# design.net
KiCad netlist of a schematic drawn in EasyEDA
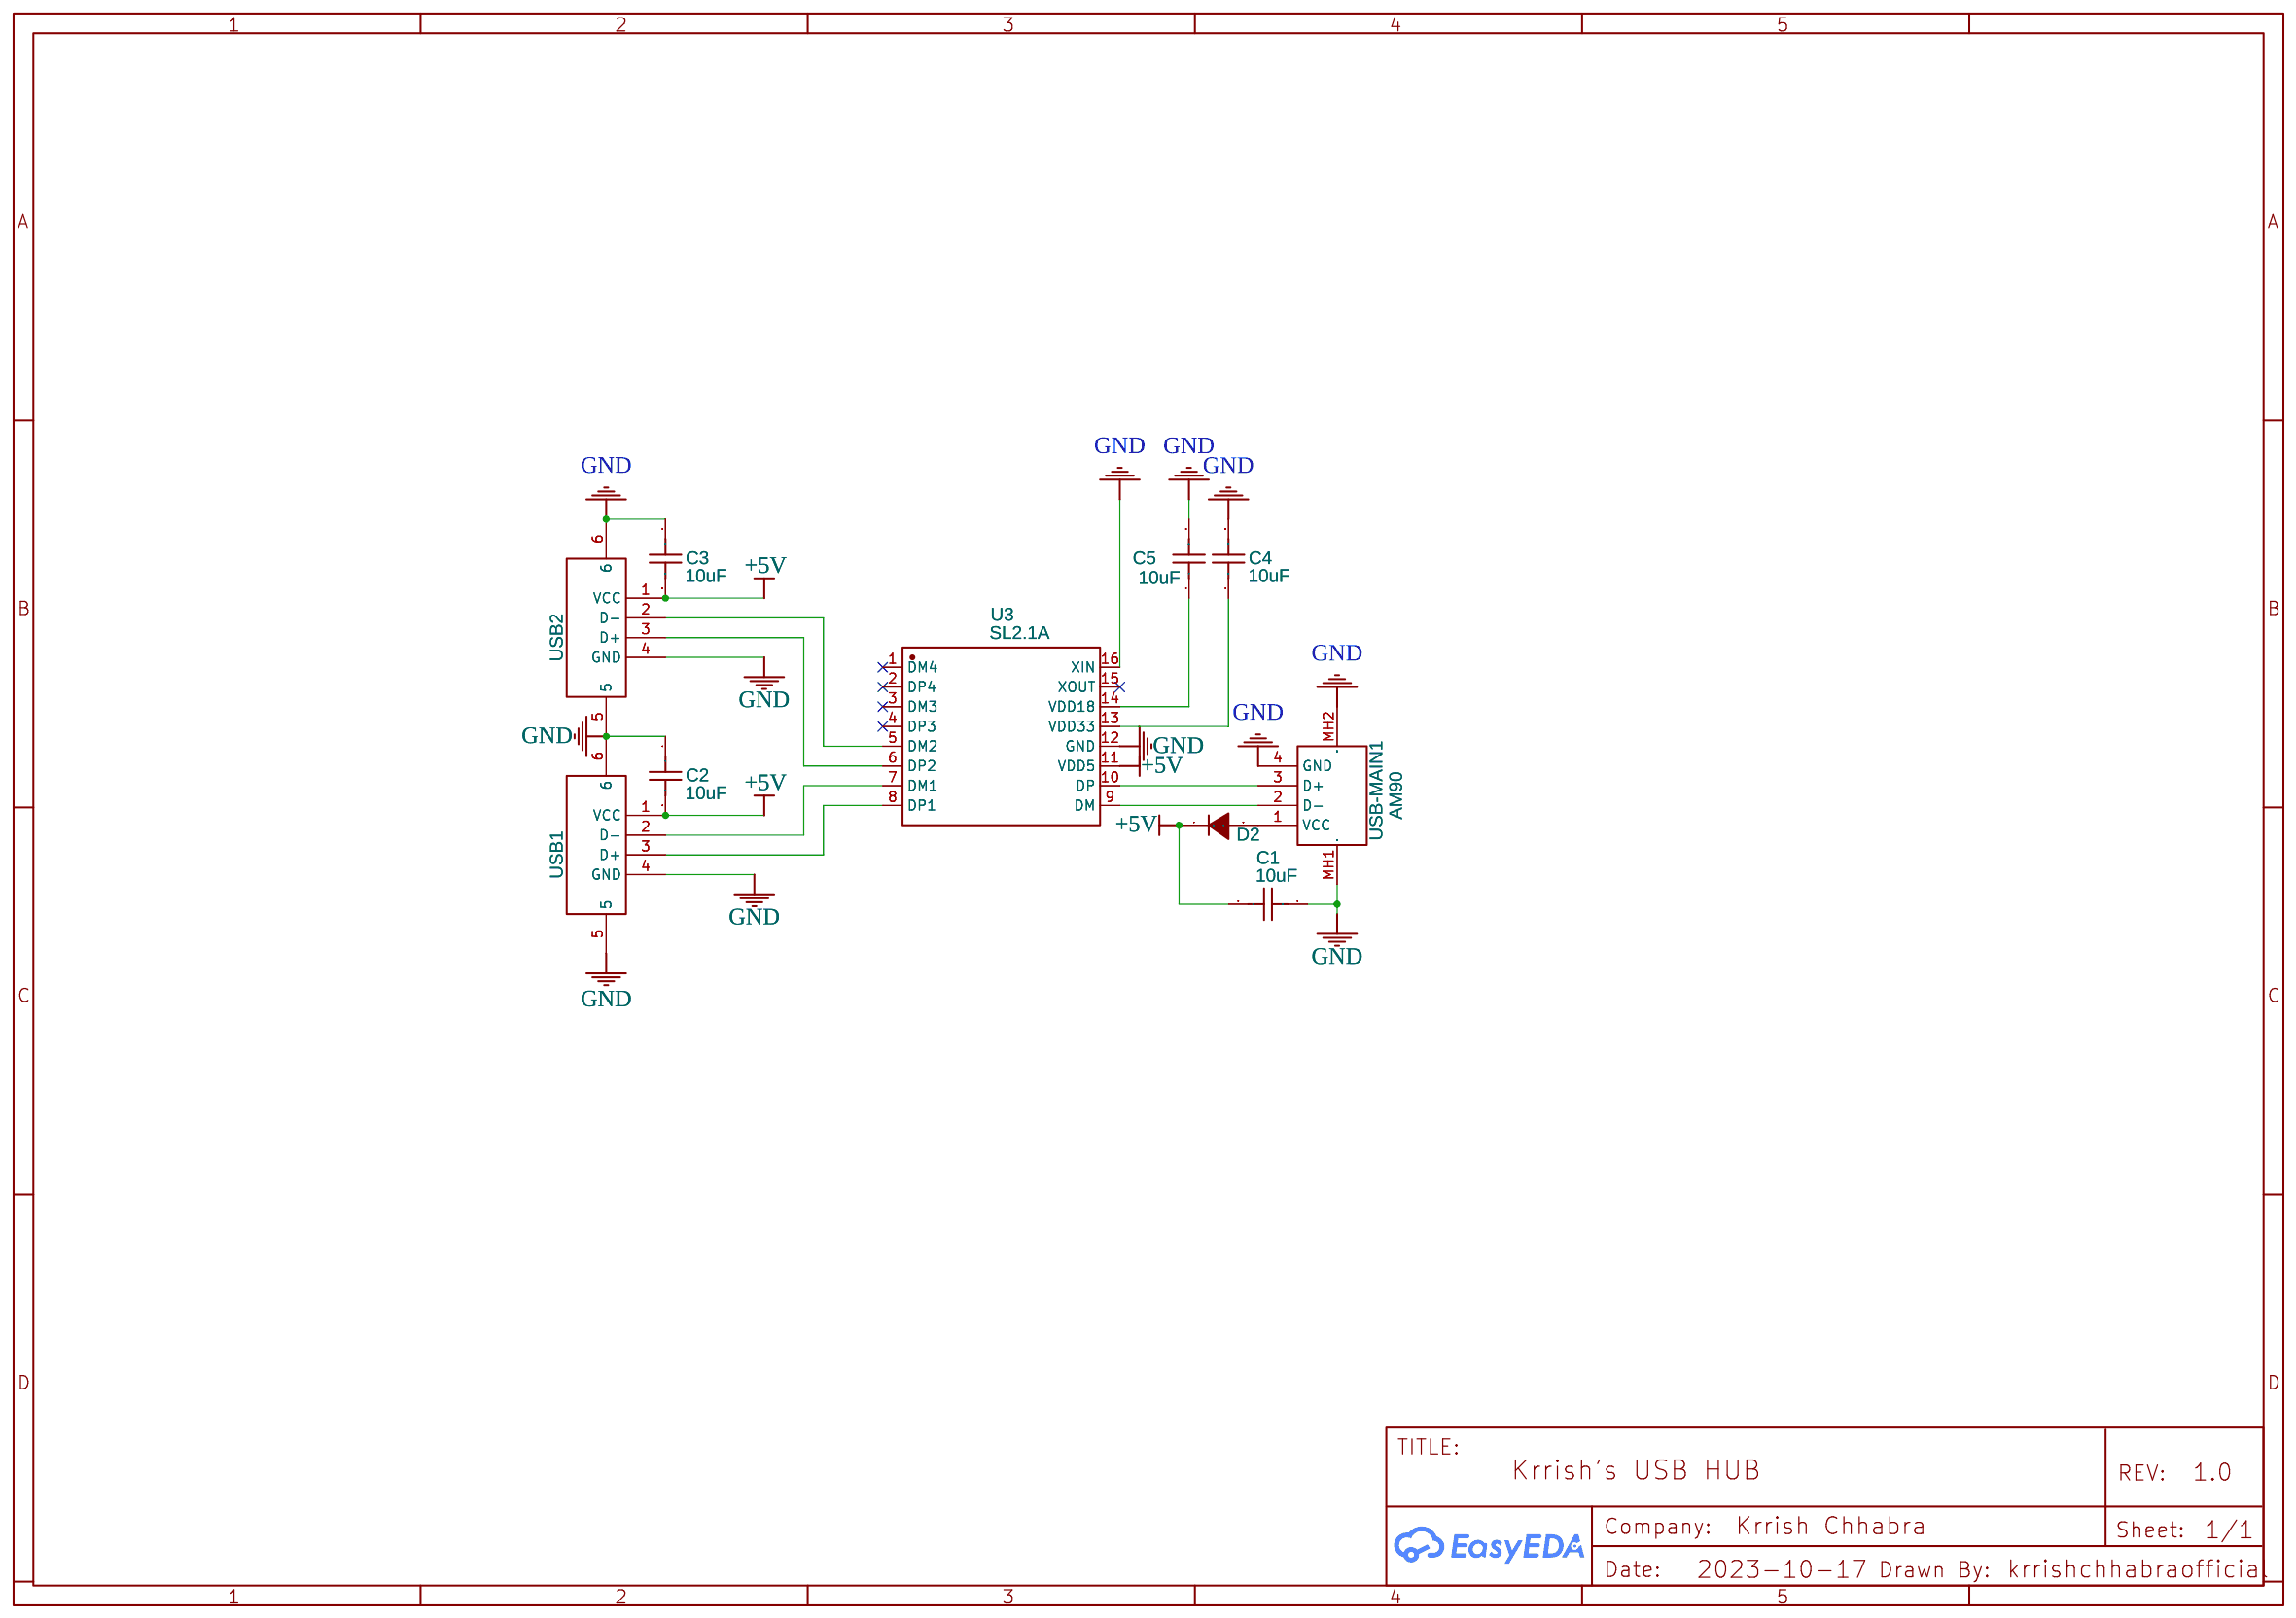
[diagram p0: schematic sheet]

(export (version "E")
  (design (tool "Eeschema 10.0.6"))
  (components
    (comp (ref "C1")
      (value "10uF")
      (fields
        (field (name "Manufacturer Part") "CL10A106KP8NNNC")
        (field (name "Manufacturer") "SAMSUNG(三星)")
      )
      (libsource (lib "") (part "CL10A106KP8NNNC_1"))
    )
    (comp (ref "C2")
      (value "10uF")
      (fields
        (field (name "Manufacturer Part") "CL10A106KP8NNNC")
        (field (name "Manufacturer") "SAMSUNG(三星)")
      )
      (libsource (lib "") (part "CL10A106KP8NNNC"))
    )
    (comp (ref "C3")
      (value "10uF")
      (fields
        (field (name "Manufacturer Part") "CL10A106KP8NNNC")
        (field (name "Manufacturer") "SAMSUNG(三星)")
      )
      (libsource (lib "") (part "CL10A106KP8NNNC"))
    )
    (comp (ref "C4") (value "10uF") (libsource (lib "") (part "C_0603_US")))
    (comp (ref "C5") (value "10uF") (libsource (lib "") (part "C_0603_US")))
    (comp (ref "D2")
      (value "NSR0320MW2T1G")
      (fields (field (name "Manufacturer") "onsemi(安森美)"))
      (libsource (lib "") (part "NSR0320MW2T1G"))
    )
    (comp (ref "U3")
      (value "SL2.1A")
      (fields (field (name "Manufacturer") "CoreChips(和芯润德)"))
      (libsource (lib "") (part "SL2.1A"))
    )
    (comp (ref "USB-MAIN1")
      (value "AM90")
      (fields (field (name "Manufacturer") "SHOU HAN(首韩)"))
      (libsource (lib "") (part "AM90"))
    )
    (comp (ref "USB1")
      (value "USB-AF-90-14.4X13.6-H7.0-DIP")
      (fields (field (name "Manufacturer Part") "903-131A1011D10100") (field (name "Manufacturer") "精拓金"))
      (libsource (lib "") (part "USB-AF-90-14.4X13.6-H7.0-DIP"))
    )
    (comp (ref "USB2")
      (value "USB-AF-90-14.4X13.6-H7.0-DIP")
      (fields (field (name "Manufacturer Part") "903-131A1011D10100") (field (name "Manufacturer") "精拓金"))
      (libsource (lib "") (part "USB-AF-90-14.4X13.6-H7.0-DIP"))
    )
  )
  (nets
    (net (code "1") (name "+5V") (class "Default")
      (node (ref "C1") (pin "2") (pinfunction "2_2") (pintype "unspecified"))
      (node (ref "C2") (pin "2") (pinfunction "2_2") (pintype "unspecified"))
      (node (ref "C3") (pin "2") (pinfunction "2_2") (pintype "unspecified"))
      (node (ref "D2") (pin "1") (pinfunction "C_1") (pintype "unspecified"))
      (node (ref "U3") (pin "11") (pinfunction "VDD5_11") (pintype "unspecified"))
      (node (ref "USB1") (pin "1") (pinfunction "VCC_1") (pintype "unspecified"))
      (node (ref "USB2") (pin "1") (pinfunction "VCC_1") (pintype "unspecified"))
    )
    (net (code "2") (name "GND") (class "Default")
      (node (ref "C1") (pin "1") (pinfunction "1_1") (pintype "unspecified"))
      (node (ref "C2") (pin "1") (pinfunction "1_1") (pintype "unspecified"))
      (node (ref "C3") (pin "1") (pinfunction "1_1") (pintype "unspecified"))
      (node (ref "C4") (pin "2") (pinfunction "2_2") (pintype "unspecified"))
      (node (ref "C5") (pin "2") (pinfunction "2_2") (pintype "unspecified"))
      (node (ref "U3") (pin "12") (pinfunction "GND_12") (pintype "unspecified"))
      (node (ref "U3") (pin "16") (pinfunction "XIN_16") (pintype "unspecified"))
      (node (ref "USB-MAIN1") (pin "4") (pinfunction "GND_4") (pintype "input"))
      (node (ref "USB-MAIN1") (pin "MH1") (pinfunction "MH1_MH1") (pintype "unspecified"))
      (node (ref "USB-MAIN1") (pin "MH2") (pinfunction "MH2_MH2") (pintype "unspecified"))
      (node (ref "USB1") (pin "4") (pinfunction "GND_4") (pintype "unspecified"))
      (node (ref "USB1") (pin "5") (pinfunction "5_5") (pintype "unspecified"))
      (node (ref "USB1") (pin "6") (pinfunction "6_6") (pintype "unspecified"))
      (node (ref "USB2") (pin "4") (pinfunction "GND_4") (pintype "unspecified"))
      (node (ref "USB2") (pin "5") (pinfunction "5_5") (pintype "unspecified"))
      (node (ref "USB2") (pin "6") (pinfunction "6_6") (pintype "unspecified"))
    )
    (net (code "3") (name "Net-(D2-A)") (class "Default")
      (node (ref "D2") (pin "2") (pinfunction "A_2") (pintype "unspecified"))
      (node (ref "USB-MAIN1") (pin "1") (pinfunction "VCC_1") (pintype "input"))
    )
    (net (code "4") (name "Net-(U3-DM)") (class "Default")
      (node (ref "U3") (pin "9") (pinfunction "DM_9") (pintype "unspecified"))
      (node (ref "USB-MAIN1") (pin "2") (pinfunction "D-_2") (pintype "input"))
    )
    (net (code "5") (name "Net-(U3-DM1)") (class "Default")
      (node (ref "U3") (pin "7") (pinfunction "DM1_7") (pintype "unspecified"))
      (node (ref "USB1") (pin "2") (pinfunction "D-_2") (pintype "unspecified"))
    )
    (net (code "6") (name "Net-(U3-DM2)") (class "Default")
      (node (ref "U3") (pin "5") (pinfunction "DM2_5") (pintype "unspecified"))
      (node (ref "USB2") (pin "2") (pinfunction "D-_2") (pintype "unspecified"))
    )
    (net (code "7") (name "Net-(U3-DP)") (class "Default")
      (node (ref "U3") (pin "10") (pinfunction "DP_10") (pintype "unspecified"))
      (node (ref "USB-MAIN1") (pin "3") (pinfunction "D+_3") (pintype "input"))
    )
    (net (code "8") (name "Net-(U3-DP1)") (class "Default")
      (node (ref "U3") (pin "8") (pinfunction "DP1_8") (pintype "unspecified"))
      (node (ref "USB1") (pin "3") (pinfunction "D+_3") (pintype "unspecified"))
    )
    (net (code "9") (name "Net-(U3-DP2)") (class "Default")
      (node (ref "U3") (pin "6") (pinfunction "DP2_6") (pintype "unspecified"))
      (node (ref "USB2") (pin "3") (pinfunction "D+_3") (pintype "unspecified"))
    )
    (net (code "10") (name "Net-(U3-VDD18)") (class "Default")
      (node (ref "C5") (pin "1") (pinfunction "1_1") (pintype "unspecified"))
      (node (ref "U3") (pin "14") (pinfunction "VDD18_14") (pintype "unspecified"))
    )
    (net (code "11") (name "Net-(U3-VDD33)") (class "Default")
      (node (ref "C4") (pin "1") (pinfunction "1_1") (pintype "unspecified"))
      (node (ref "U3") (pin "13") (pinfunction "VDD33_13") (pintype "unspecified"))
    )
    (net (code "12") (name "unconnected-(U3-DM3-Pad3)") (class "Default")
      (node (ref "U3") (pin "3") (pinfunction "DM3_3") (pintype "unspecified+no_connect"))
    )
    (net (code "13") (name "unconnected-(U3-DM4-Pad1)") (class "Default")
      (node (ref "U3") (pin "1") (pinfunction "DM4_1") (pintype "unspecified+no_connect"))
    )
    (net (code "14") (name "unconnected-(U3-DP3-Pad4)") (class "Default")
      (node (ref "U3") (pin "4") (pinfunction "DP3_4") (pintype "unspecified+no_connect"))
    )
    (net (code "15") (name "unconnected-(U3-DP4-Pad2)") (class "Default")
      (node (ref "U3") (pin "2") (pinfunction "DP4_2") (pintype "unspecified+no_connect"))
    )
    (net (code "16") (name "unconnected-(U3-XOUT-Pad15)") (class "Default")
      (node (ref "U3") (pin "15") (pinfunction "XOUT_15") (pintype "unspecified+no_connect"))
    )
  )
)
